# BigFrontplane.net
KiCad netlist of a schematic drawn in EAGLE
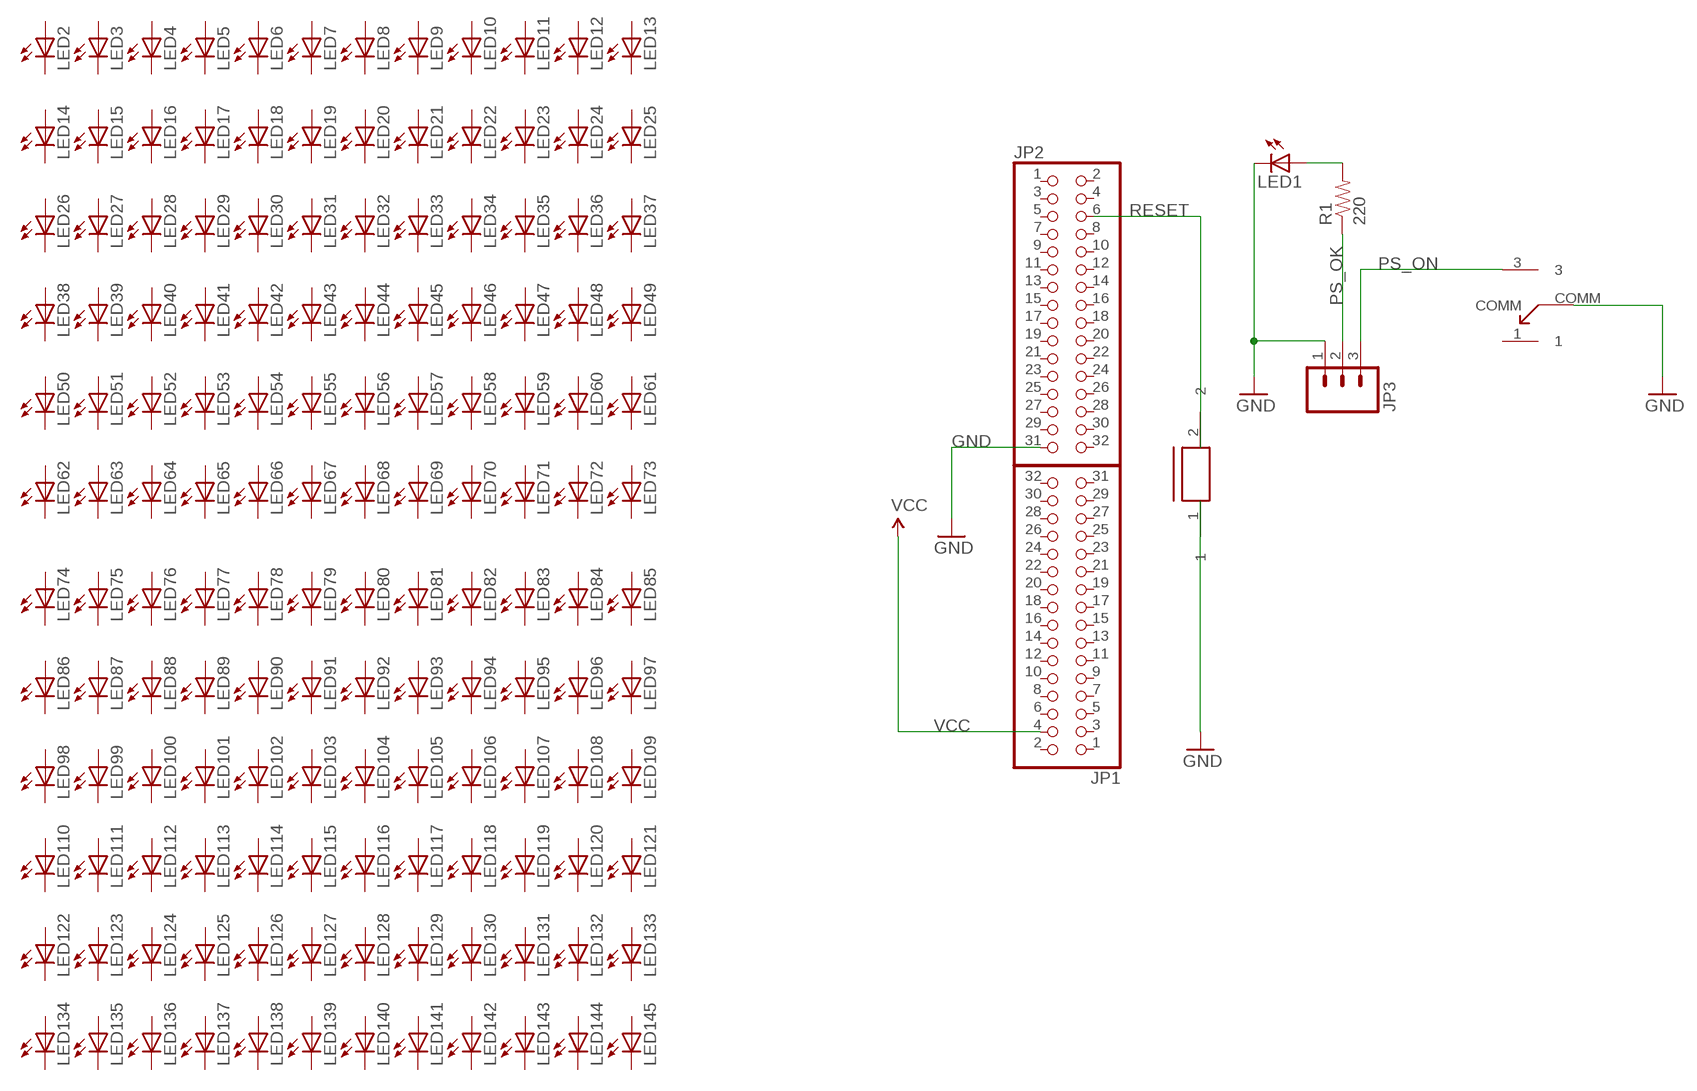
[diagram p0: schematic, sheet 1]

(export (version "E")
  (design (tool "Eeschema 10.0.6"))
  (components
    (comp (ref "JP1")
      (value "PINHD-2X16")
      (footprint "eagle-import:2X16")
      (libsource (lib "eagle-import") (part "PINHD-2X16"))
    )
    (comp (ref "JP2")
      (value "PINHD-2X16")
      (footprint "eagle-import:2X16")
      (libsource (lib "eagle-import") (part "PINHD-2X16"))
    )
    (comp (ref "JP3")
      (value "M03LONGPADS")
      (footprint "eagle-import:1X03_LONGPADS")
      (libsource (lib "eagle-import") (part "M03LONGPADS"))
    )
    (comp (ref "LED1")
      (value "LED5MM")
      (footprint "eagle-import:LED5MM")
      (libsource (lib "eagle-import") (part "led_LED5MM"))
    )
    (comp (ref "LED2")
      (value "LED3MM")
      (footprint "eagle-import:LED3MM")
      (libsource (lib "eagle-import") (part "LED3MM"))
    )
    (comp (ref "LED3")
      (value "LED3MM")
      (footprint "eagle-import:LED3MM")
      (libsource (lib "eagle-import") (part "LED3MM"))
    )
    (comp (ref "LED4")
      (value "LED3MM")
      (footprint "eagle-import:LED3MM")
      (libsource (lib "eagle-import") (part "LED3MM"))
    )
    (comp (ref "LED5")
      (value "LED3MM")
      (footprint "eagle-import:LED3MM")
      (libsource (lib "eagle-import") (part "LED3MM"))
    )
    (comp (ref "LED6")
      (value "LED3MM")
      (footprint "eagle-import:LED3MM")
      (libsource (lib "eagle-import") (part "LED3MM"))
    )
    (comp (ref "LED7")
      (value "LED3MM")
      (footprint "eagle-import:LED3MM")
      (libsource (lib "eagle-import") (part "LED3MM"))
    )
    (comp (ref "LED8")
      (value "LED3MM")
      (footprint "eagle-import:LED3MM")
      (libsource (lib "eagle-import") (part "LED3MM"))
    )
    (comp (ref "LED9")
      (value "LED3MM")
      (footprint "eagle-import:LED3MM")
      (libsource (lib "eagle-import") (part "LED3MM"))
    )
    (comp (ref "LED10")
      (value "LED3MM")
      (footprint "eagle-import:LED3MM")
      (libsource (lib "eagle-import") (part "LED3MM"))
    )
    (comp (ref "LED11")
      (value "LED3MM")
      (footprint "eagle-import:LED3MM")
      (libsource (lib "eagle-import") (part "LED3MM"))
    )
    (comp (ref "LED12")
      (value "LED3MM")
      (footprint "eagle-import:LED3MM")
      (libsource (lib "eagle-import") (part "LED3MM"))
    )
    (comp (ref "LED13")
      (value "LED3MM")
      (footprint "eagle-import:LED3MM")
      (libsource (lib "eagle-import") (part "LED3MM"))
    )
    (comp (ref "LED14")
      (value "LED3MM")
      (footprint "eagle-import:LED3MM")
      (libsource (lib "eagle-import") (part "LED3MM"))
    )
    (comp (ref "LED15")
      (value "LED3MM")
      (footprint "eagle-import:LED3MM")
      (libsource (lib "eagle-import") (part "LED3MM"))
    )
    (comp (ref "LED16")
      (value "LED3MM")
      (footprint "eagle-import:LED3MM")
      (libsource (lib "eagle-import") (part "LED3MM"))
    )
    (comp (ref "LED17")
      (value "LED3MM")
      (footprint "eagle-import:LED3MM")
      (libsource (lib "eagle-import") (part "LED3MM"))
    )
    (comp (ref "LED18")
      (value "LED3MM")
      (footprint "eagle-import:LED3MM")
      (libsource (lib "eagle-import") (part "LED3MM"))
    )
    (comp (ref "LED19")
      (value "LED3MM")
      (footprint "eagle-import:LED3MM")
      (libsource (lib "eagle-import") (part "LED3MM"))
    )
    (comp (ref "LED20")
      (value "LED3MM")
      (footprint "eagle-import:LED3MM")
      (libsource (lib "eagle-import") (part "LED3MM"))
    )
    (comp (ref "LED21")
      (value "LED3MM")
      (footprint "eagle-import:LED3MM")
      (libsource (lib "eagle-import") (part "LED3MM"))
    )
    (comp (ref "LED22")
      (value "LED3MM")
      (footprint "eagle-import:LED3MM")
      (libsource (lib "eagle-import") (part "LED3MM"))
    )
    (comp (ref "LED23")
      (value "LED3MM")
      (footprint "eagle-import:LED3MM")
      (libsource (lib "eagle-import") (part "LED3MM"))
    )
    (comp (ref "LED24")
      (value "LED3MM")
      (footprint "eagle-import:LED3MM")
      (libsource (lib "eagle-import") (part "LED3MM"))
    )
    (comp (ref "LED25")
      (value "LED3MM")
      (footprint "eagle-import:LED3MM")
      (libsource (lib "eagle-import") (part "LED3MM"))
    )
    (comp (ref "LED26")
      (value "LED3MM")
      (footprint "eagle-import:LED3MM")
      (libsource (lib "eagle-import") (part "LED3MM"))
    )
    (comp (ref "LED27")
      (value "LED3MM")
      (footprint "eagle-import:LED3MM")
      (libsource (lib "eagle-import") (part "LED3MM"))
    )
    (comp (ref "LED28")
      (value "LED3MM")
      (footprint "eagle-import:LED3MM")
      (libsource (lib "eagle-import") (part "LED3MM"))
    )
    (comp (ref "LED29")
      (value "LED3MM")
      (footprint "eagle-import:LED3MM")
      (libsource (lib "eagle-import") (part "LED3MM"))
    )
    (comp (ref "LED30")
      (value "LED3MM")
      (footprint "eagle-import:LED3MM")
      (libsource (lib "eagle-import") (part "LED3MM"))
    )
    (comp (ref "LED31")
      (value "LED3MM")
      (footprint "eagle-import:LED3MM")
      (libsource (lib "eagle-import") (part "LED3MM"))
    )
    (comp (ref "LED32")
      (value "LED3MM")
      (footprint "eagle-import:LED3MM")
      (libsource (lib "eagle-import") (part "LED3MM"))
    )
    (comp (ref "LED33")
      (value "LED3MM")
      (footprint "eagle-import:LED3MM")
      (libsource (lib "eagle-import") (part "LED3MM"))
    )
    (comp (ref "LED34")
      (value "LED3MM")
      (footprint "eagle-import:LED3MM")
      (libsource (lib "eagle-import") (part "LED3MM"))
    )
    (comp (ref "LED35")
      (value "LED3MM")
      (footprint "eagle-import:LED3MM")
      (libsource (lib "eagle-import") (part "LED3MM"))
    )
    (comp (ref "LED36")
      (value "LED3MM")
      (footprint "eagle-import:LED3MM")
      (libsource (lib "eagle-import") (part "LED3MM"))
    )
    (comp (ref "LED37")
      (value "LED3MM")
      (footprint "eagle-import:LED3MM")
      (libsource (lib "eagle-import") (part "LED3MM"))
    )
    (comp (ref "LED38")
      (value "LED3MM")
      (footprint "eagle-import:LED3MM")
      (libsource (lib "eagle-import") (part "LED3MM"))
    )
    (comp (ref "LED39")
      (value "LED3MM")
      (footprint "eagle-import:LED3MM")
      (libsource (lib "eagle-import") (part "LED3MM"))
    )
    (comp (ref "LED40")
      (value "LED3MM")
      (footprint "eagle-import:LED3MM")
      (libsource (lib "eagle-import") (part "LED3MM"))
    )
    (comp (ref "LED41")
      (value "LED3MM")
      (footprint "eagle-import:LED3MM")
      (libsource (lib "eagle-import") (part "LED3MM"))
    )
    (comp (ref "LED42")
      (value "LED3MM")
      (footprint "eagle-import:LED3MM")
      (libsource (lib "eagle-import") (part "LED3MM"))
    )
    (comp (ref "LED43")
      (value "LED3MM")
      (footprint "eagle-import:LED3MM")
      (libsource (lib "eagle-import") (part "LED3MM"))
    )
    (comp (ref "LED44")
      (value "LED3MM")
      (footprint "eagle-import:LED3MM")
      (libsource (lib "eagle-import") (part "LED3MM"))
    )
    (comp (ref "LED45")
      (value "LED3MM")
      (footprint "eagle-import:LED3MM")
      (libsource (lib "eagle-import") (part "LED3MM"))
    )
    (comp (ref "LED46")
      (value "LED3MM")
      (footprint "eagle-import:LED3MM")
      (libsource (lib "eagle-import") (part "LED3MM"))
    )
    (comp (ref "LED47")
      (value "LED3MM")
      (footprint "eagle-import:LED3MM")
      (libsource (lib "eagle-import") (part "LED3MM"))
    )
    (comp (ref "LED48")
      (value "LED3MM")
      (footprint "eagle-import:LED3MM")
      (libsource (lib "eagle-import") (part "LED3MM"))
    )
    (comp (ref "LED49")
      (value "LED3MM")
      (footprint "eagle-import:LED3MM")
      (libsource (lib "eagle-import") (part "LED3MM"))
    )
    (comp (ref "LED50")
      (value "LED3MM")
      (footprint "eagle-import:LED3MM")
      (libsource (lib "eagle-import") (part "LED3MM"))
    )
    (comp (ref "LED51")
      (value "LED3MM")
      (footprint "eagle-import:LED3MM")
      (libsource (lib "eagle-import") (part "LED3MM"))
    )
    (comp (ref "LED52")
      (value "LED3MM")
      (footprint "eagle-import:LED3MM")
      (libsource (lib "eagle-import") (part "LED3MM"))
    )
    (comp (ref "LED53")
      (value "LED3MM")
      (footprint "eagle-import:LED3MM")
      (libsource (lib "eagle-import") (part "LED3MM"))
    )
    (comp (ref "LED54")
      (value "LED3MM")
      (footprint "eagle-import:LED3MM")
      (libsource (lib "eagle-import") (part "LED3MM"))
    )
    (comp (ref "LED55")
      (value "LED3MM")
      (footprint "eagle-import:LED3MM")
      (libsource (lib "eagle-import") (part "LED3MM"))
    )
    (comp (ref "LED56")
      (value "LED3MM")
      (footprint "eagle-import:LED3MM")
      (libsource (lib "eagle-import") (part "LED3MM"))
    )
    (comp (ref "LED57")
      (value "LED3MM")
      (footprint "eagle-import:LED3MM")
      (libsource (lib "eagle-import") (part "LED3MM"))
    )
    (comp (ref "LED58")
      (value "LED3MM")
      (footprint "eagle-import:LED3MM")
      (libsource (lib "eagle-import") (part "LED3MM"))
    )
    (comp (ref "LED59")
      (value "LED3MM")
      (footprint "eagle-import:LED3MM")
      (libsource (lib "eagle-import") (part "LED3MM"))
    )
    (comp (ref "LED60")
      (value "LED3MM")
      (footprint "eagle-import:LED3MM")
      (libsource (lib "eagle-import") (part "LED3MM"))
    )
    (comp (ref "LED61")
      (value "LED3MM")
      (footprint "eagle-import:LED3MM")
      (libsource (lib "eagle-import") (part "LED3MM"))
    )
    (comp (ref "LED62")
      (value "LED3MM")
      (footprint "eagle-import:LED3MM")
      (libsource (lib "eagle-import") (part "LED3MM"))
    )
    (comp (ref "LED63")
      (value "LED3MM")
      (footprint "eagle-import:LED3MM")
      (libsource (lib "eagle-import") (part "LED3MM"))
    )
    (comp (ref "LED64")
      (value "LED3MM")
      (footprint "eagle-import:LED3MM")
      (libsource (lib "eagle-import") (part "LED3MM"))
    )
    (comp (ref "LED65")
      (value "LED3MM")
      (footprint "eagle-import:LED3MM")
      (libsource (lib "eagle-import") (part "LED3MM"))
    )
    (comp (ref "LED66")
      (value "LED3MM")
      (footprint "eagle-import:LED3MM")
      (libsource (lib "eagle-import") (part "LED3MM"))
    )
    (comp (ref "LED67")
      (value "LED3MM")
      (footprint "eagle-import:LED3MM")
      (libsource (lib "eagle-import") (part "LED3MM"))
    )
    (comp (ref "LED68")
      (value "LED3MM")
      (footprint "eagle-import:LED3MM")
      (libsource (lib "eagle-import") (part "LED3MM"))
    )
    (comp (ref "LED69")
      (value "LED3MM")
      (footprint "eagle-import:LED3MM")
      (libsource (lib "eagle-import") (part "LED3MM"))
    )
    (comp (ref "LED70")
      (value "LED3MM")
      (footprint "eagle-import:LED3MM")
      (libsource (lib "eagle-import") (part "LED3MM"))
    )
    (comp (ref "LED71")
      (value "LED3MM")
      (footprint "eagle-import:LED3MM")
      (libsource (lib "eagle-import") (part "LED3MM"))
    )
    (comp (ref "LED72")
      (value "LED3MM")
      (footprint "eagle-import:LED3MM")
      (libsource (lib "eagle-import") (part "LED3MM"))
    )
    (comp (ref "LED73")
      (value "LED3MM")
      (footprint "eagle-import:LED3MM")
      (libsource (lib "eagle-import") (part "LED3MM"))
    )
    (comp (ref "LED74")
      (value "LED3MM")
      (footprint "eagle-import:LED3MM")
      (libsource (lib "eagle-import") (part "LED3MM"))
    )
    (comp (ref "LED75")
      (value "LED3MM")
      (footprint "eagle-import:LED3MM")
      (libsource (lib "eagle-import") (part "LED3MM"))
    )
    (comp (ref "LED76")
      (value "LED3MM")
      (footprint "eagle-import:LED3MM")
      (libsource (lib "eagle-import") (part "LED3MM"))
    )
    (comp (ref "LED77")
      (value "LED3MM")
      (footprint "eagle-import:LED3MM")
      (libsource (lib "eagle-import") (part "LED3MM"))
    )
    (comp (ref "LED78")
      (value "LED3MM")
      (footprint "eagle-import:LED3MM")
      (libsource (lib "eagle-import") (part "LED3MM"))
    )
    (comp (ref "LED79")
      (value "LED3MM")
      (footprint "eagle-import:LED3MM")
      (libsource (lib "eagle-import") (part "LED3MM"))
    )
    (comp (ref "LED80")
      (value "LED3MM")
      (footprint "eagle-import:LED3MM")
      (libsource (lib "eagle-import") (part "LED3MM"))
    )
    (comp (ref "LED81")
      (value "LED3MM")
      (footprint "eagle-import:LED3MM")
      (libsource (lib "eagle-import") (part "LED3MM"))
    )
    (comp (ref "LED82")
      (value "LED3MM")
      (footprint "eagle-import:LED3MM")
      (libsource (lib "eagle-import") (part "LED3MM"))
    )
    (comp (ref "LED83")
      (value "LED3MM")
      (footprint "eagle-import:LED3MM")
      (libsource (lib "eagle-import") (part "LED3MM"))
    )
    (comp (ref "LED84")
      (value "LED3MM")
      (footprint "eagle-import:LED3MM")
      (libsource (lib "eagle-import") (part "LED3MM"))
    )
    (comp (ref "LED85")
      (value "LED3MM")
      (footprint "eagle-import:LED3MM")
      (libsource (lib "eagle-import") (part "LED3MM"))
    )
    (comp (ref "LED86")
      (value "LED3MM")
      (footprint "eagle-import:LED3MM")
      (libsource (lib "eagle-import") (part "LED3MM"))
    )
    (comp (ref "LED87")
      (value "LED3MM")
      (footprint "eagle-import:LED3MM")
      (libsource (lib "eagle-import") (part "LED3MM"))
    )
    (comp (ref "LED88")
      (value "LED3MM")
      (footprint "eagle-import:LED3MM")
      (libsource (lib "eagle-import") (part "LED3MM"))
    )
    (comp (ref "LED89")
      (value "LED3MM")
      (footprint "eagle-import:LED3MM")
      (libsource (lib "eagle-import") (part "LED3MM"))
    )
    (comp (ref "LED90")
      (value "LED3MM")
      (footprint "eagle-import:LED3MM")
      (libsource (lib "eagle-import") (part "LED3MM"))
    )
    (comp (ref "LED91")
      (value "LED3MM")
      (footprint "eagle-import:LED3MM")
      (libsource (lib "eagle-import") (part "LED3MM"))
    )
    (comp (ref "LED92")
      (value "LED3MM")
      (footprint "eagle-import:LED3MM")
      (libsource (lib "eagle-import") (part "LED3MM"))
    )
    (comp (ref "LED93")
      (value "LED3MM")
      (footprint "eagle-import:LED3MM")
      (libsource (lib "eagle-import") (part "LED3MM"))
    )
    (comp (ref "LED94")
      (value "LED3MM")
      (footprint "eagle-import:LED3MM")
      (libsource (lib "eagle-import") (part "LED3MM"))
    )
    (comp (ref "LED95")
      (value "LED3MM")
      (footprint "eagle-import:LED3MM")
      (libsource (lib "eagle-import") (part "LED3MM"))
    )
    (comp (ref "LED96")
      (value "LED3MM")
      (footprint "eagle-import:LED3MM")
      (libsource (lib "eagle-import") (part "LED3MM"))
    )
    (comp (ref "LED97")
      (value "LED3MM")
      (footprint "eagle-import:LED3MM")
      (libsource (lib "eagle-import") (part "LED3MM"))
    )
    (comp (ref "LED98")
      (value "LED3MM")
      (footprint "eagle-import:LED3MM")
      (libsource (lib "eagle-import") (part "LED3MM"))
    )
    (comp (ref "LED99")
      (value "LED3MM")
      (footprint "eagle-import:LED3MM")
      (libsource (lib "eagle-import") (part "LED3MM"))
    )
    (comp (ref "LED100")
      (value "LED3MM")
      (footprint "eagle-import:LED3MM")
      (libsource (lib "eagle-import") (part "LED3MM"))
    )
    (comp (ref "LED101")
      (value "LED3MM")
      (footprint "eagle-import:LED3MM")
      (libsource (lib "eagle-import") (part "LED3MM"))
    )
    (comp (ref "LED102")
      (value "LED3MM")
      (footprint "eagle-import:LED3MM")
      (libsource (lib "eagle-import") (part "LED3MM"))
    )
    (comp (ref "LED103")
      (value "LED3MM")
      (footprint "eagle-import:LED3MM")
      (libsource (lib "eagle-import") (part "LED3MM"))
    )
    (comp (ref "LED104")
      (value "LED3MM")
      (footprint "eagle-import:LED3MM")
      (libsource (lib "eagle-import") (part "LED3MM"))
    )
    (comp (ref "LED105")
      (value "LED3MM")
      (footprint "eagle-import:LED3MM")
      (libsource (lib "eagle-import") (part "LED3MM"))
    )
    (comp (ref "LED106")
      (value "LED3MM")
      (footprint "eagle-import:LED3MM")
      (libsource (lib "eagle-import") (part "LED3MM"))
    )
    (comp (ref "LED107")
      (value "LED3MM")
      (footprint "eagle-import:LED3MM")
      (libsource (lib "eagle-import") (part "LED3MM"))
    )
    (comp (ref "LED108")
      (value "LED3MM")
      (footprint "eagle-import:LED3MM")
      (libsource (lib "eagle-import") (part "LED3MM"))
    )
    (comp (ref "LED109")
      (value "LED3MM")
      (footprint "eagle-import:LED3MM")
      (libsource (lib "eagle-import") (part "LED3MM"))
    )
    (comp (ref "LED110")
      (value "LED3MM")
      (footprint "eagle-import:LED3MM")
      (libsource (lib "eagle-import") (part "LED3MM"))
    )
    (comp (ref "LED111")
      (value "LED3MM")
      (footprint "eagle-import:LED3MM")
      (libsource (lib "eagle-import") (part "LED3MM"))
    )
    (comp (ref "LED112")
      (value "LED3MM")
      (footprint "eagle-import:LED3MM")
      (libsource (lib "eagle-import") (part "LED3MM"))
    )
    (comp (ref "LED113")
      (value "LED3MM")
      (footprint "eagle-import:LED3MM")
      (libsource (lib "eagle-import") (part "LED3MM"))
    )
    (comp (ref "LED114")
      (value "LED3MM")
      (footprint "eagle-import:LED3MM")
      (libsource (lib "eagle-import") (part "LED3MM"))
    )
    (comp (ref "LED115")
      (value "LED3MM")
      (footprint "eagle-import:LED3MM")
      (libsource (lib "eagle-import") (part "LED3MM"))
    )
    (comp (ref "LED116")
      (value "LED3MM")
      (footprint "eagle-import:LED3MM")
      (libsource (lib "eagle-import") (part "LED3MM"))
    )
    (comp (ref "LED117")
      (value "LED3MM")
      (footprint "eagle-import:LED3MM")
      (libsource (lib "eagle-import") (part "LED3MM"))
    )
    (comp (ref "LED118")
      (value "LED3MM")
      (footprint "eagle-import:LED3MM")
      (libsource (lib "eagle-import") (part "LED3MM"))
    )
    (comp (ref "LED119")
      (value "LED3MM")
      (footprint "eagle-import:LED3MM")
      (libsource (lib "eagle-import") (part "LED3MM"))
    )
    (comp (ref "LED120")
      (value "LED3MM")
      (footprint "eagle-import:LED3MM")
      (libsource (lib "eagle-import") (part "LED3MM"))
    )
    (comp (ref "LED121")
      (value "LED3MM")
      (footprint "eagle-import:LED3MM")
      (libsource (lib "eagle-import") (part "LED3MM"))
    )
    (comp (ref "LED122")
      (value "LED3MM")
      (footprint "eagle-import:LED3MM")
      (libsource (lib "eagle-import") (part "LED3MM"))
    )
    (comp (ref "LED123")
      (value "LED3MM")
      (footprint "eagle-import:LED3MM")
      (libsource (lib "eagle-import") (part "LED3MM"))
    )
    (comp (ref "LED124")
      (value "LED3MM")
      (footprint "eagle-import:LED3MM")
      (libsource (lib "eagle-import") (part "LED3MM"))
    )
    (comp (ref "LED125")
      (value "LED3MM")
      (footprint "eagle-import:LED3MM")
      (libsource (lib "eagle-import") (part "LED3MM"))
    )
    (comp (ref "LED126")
      (value "LED3MM")
      (footprint "eagle-import:LED3MM")
      (libsource (lib "eagle-import") (part "LED3MM"))
    )
    (comp (ref "LED127")
      (value "LED3MM")
      (footprint "eagle-import:LED3MM")
      (libsource (lib "eagle-import") (part "LED3MM"))
    )
    (comp (ref "LED128")
      (value "LED3MM")
      (footprint "eagle-import:LED3MM")
      (libsource (lib "eagle-import") (part "LED3MM"))
    )
    (comp (ref "LED129")
      (value "LED3MM")
      (footprint "eagle-import:LED3MM")
      (libsource (lib "eagle-import") (part "LED3MM"))
    )
    (comp (ref "LED130")
      (value "LED3MM")
      (footprint "eagle-import:LED3MM")
      (libsource (lib "eagle-import") (part "LED3MM"))
    )
    (comp (ref "LED131")
      (value "LED3MM")
      (footprint "eagle-import:LED3MM")
      (libsource (lib "eagle-import") (part "LED3MM"))
    )
    (comp (ref "LED132")
      (value "LED3MM")
      (footprint "eagle-import:LED3MM")
      (libsource (lib "eagle-import") (part "LED3MM"))
    )
    (comp (ref "LED133")
      (value "LED3MM")
      (footprint "eagle-import:LED3MM")
      (libsource (lib "eagle-import") (part "LED3MM"))
    )
    (comp (ref "LED134")
      (value "LED3MM")
      (footprint "eagle-import:LED3MM")
      (libsource (lib "eagle-import") (part "LED3MM"))
    )
    (comp (ref "LED135")
      (value "LED3MM")
      (footprint "eagle-import:LED3MM")
      (libsource (lib "eagle-import") (part "LED3MM"))
    )
    (comp (ref "LED136")
      (value "LED3MM")
      (footprint "eagle-import:LED3MM")
      (libsource (lib "eagle-import") (part "LED3MM"))
    )
    (comp (ref "LED137")
      (value "LED3MM")
      (footprint "eagle-import:LED3MM")
      (libsource (lib "eagle-import") (part "LED3MM"))
    )
    (comp (ref "LED138")
      (value "LED3MM")
      (footprint "eagle-import:LED3MM")
      (libsource (lib "eagle-import") (part "LED3MM"))
    )
    (comp (ref "LED139")
      (value "LED3MM")
      (footprint "eagle-import:LED3MM")
      (libsource (lib "eagle-import") (part "LED3MM"))
    )
    (comp (ref "LED140")
      (value "LED3MM")
      (footprint "eagle-import:LED3MM")
      (libsource (lib "eagle-import") (part "LED3MM"))
    )
    (comp (ref "LED141")
      (value "LED3MM")
      (footprint "eagle-import:LED3MM")
      (libsource (lib "eagle-import") (part "LED3MM"))
    )
    (comp (ref "LED142")
      (value "LED3MM")
      (footprint "eagle-import:LED3MM")
      (libsource (lib "eagle-import") (part "LED3MM"))
    )
    (comp (ref "LED143")
      (value "LED3MM")
      (footprint "eagle-import:LED3MM")
      (libsource (lib "eagle-import") (part "LED3MM"))
    )
    (comp (ref "LED144")
      (value "LED3MM")
      (footprint "eagle-import:LED3MM")
      (libsource (lib "eagle-import") (part "LED3MM"))
    )
    (comp (ref "LED145")
      (value "LED3MM")
      (footprint "eagle-import:LED3MM")
      (libsource (lib "eagle-import") (part "LED3MM"))
    )
    (comp (ref "R1")
      (value "220")
      (footprint "eagle-import:AXIAL-0.3-KIT")
      (libsource (lib "eagle-import") (part "RESISTORKIT"))
    )
    (comp (ref "U$1")
      (value "7101")
      (footprint "eagle-import:7101SYCQE")
      (libsource (lib "eagle-import") (part "7101"))
    )
    (comp (ref "U$2")
      (value "TP11")
      (footprint "eagle-import:TP11")
      (libsource (lib "eagle-import") (part "TP11"))
    )
  )
  (nets
    (net (code "1") (name "/PS_OK") (class "Default")
      (node (ref "JP3") (pin "2") (pinfunction "2_2") (pintype "passive"))
      (node (ref "R1") (pin "P$1") (pinfunction "1_P$1") (pintype "passive"))
    )
    (net (code "2") (name "/PS_ON") (class "Default")
      (node (ref "JP3") (pin "3") (pinfunction "3_3") (pintype "passive"))
      (node (ref "U$1") (pin "3") (pinfunction "3_3") (pintype "bidirectional"))
    )
    (net (code "3") (name "/RESET") (class "Default")
      (node (ref "JP2") (pin "6") (pinfunction "6_6") (pintype "passive"))
      (node (ref "U$2") (pin "2") (pinfunction "2_2") (pintype "bidirectional"))
    )
    (net (code "4") (name "GND") (class "Default")
      (node (ref "JP2") (pin "31") (pinfunction "31_31") (pintype "passive"))
      (node (ref "JP3") (pin "1") (pinfunction "1_1") (pintype "passive"))
      (node (ref "LED1") (pin "K") (pinfunction "C_K") (pintype "passive"))
      (node (ref "U$1") (pin "COMM") (pinfunction "COMM_COMM") (pintype "bidirectional"))
      (node (ref "U$2") (pin "1") (pinfunction "1_1") (pintype "bidirectional"))
    )
    (net (code "5") (name "Net-(R1-2)") (class "Default")
      (node (ref "LED1") (pin "A") (pinfunction "A_A") (pintype "passive"))
      (node (ref "R1") (pin "P$2") (pinfunction "2_P$2") (pintype "passive"))
    )
    (net (code "6") (name "VCC") (class "Default")
      (node (ref "JP1") (pin "4") (pinfunction "4_4") (pintype "passive"))
    )
    (net (code "7") (name "unconnected-(JP1-Pad1)") (class "Default")
      (node (ref "JP1") (pin "1") (pinfunction "1_1") (pintype "passive"))
    )
    (net (code "8") (name "unconnected-(JP1-Pad2)") (class "Default")
      (node (ref "JP1") (pin "2") (pinfunction "2_2") (pintype "passive"))
    )
    (net (code "9") (name "unconnected-(JP1-Pad3)") (class "Default")
      (node (ref "JP1") (pin "3") (pinfunction "3_3") (pintype "passive"))
    )
    (net (code "10") (name "unconnected-(JP1-Pad5)") (class "Default")
      (node (ref "JP1") (pin "5") (pinfunction "5_5") (pintype "passive"))
    )
    (net (code "11") (name "unconnected-(JP1-Pad6)") (class "Default")
      (node (ref "JP1") (pin "6") (pinfunction "6_6") (pintype "passive"))
    )
    (net (code "12") (name "unconnected-(JP1-Pad7)") (class "Default")
      (node (ref "JP1") (pin "7") (pinfunction "7_7") (pintype "passive"))
    )
    (net (code "13") (name "unconnected-(JP1-Pad8)") (class "Default")
      (node (ref "JP1") (pin "8") (pinfunction "8_8") (pintype "passive"))
    )
    (net (code "14") (name "unconnected-(JP1-Pad9)") (class "Default")
      (node (ref "JP1") (pin "9") (pinfunction "9_9") (pintype "passive"))
    )
    (net (code "15") (name "unconnected-(JP1-Pad10)") (class "Default")
      (node (ref "JP1") (pin "10") (pinfunction "10_10") (pintype "passive"))
    )
    (net (code "16") (name "unconnected-(JP1-Pad11)") (class "Default")
      (node (ref "JP1") (pin "11") (pinfunction "11_11") (pintype "passive"))
    )
    (net (code "17") (name "unconnected-(JP1-Pad12)") (class "Default")
      (node (ref "JP1") (pin "12") (pinfunction "12_12") (pintype "passive"))
    )
    (net (code "18") (name "unconnected-(JP1-Pad13)") (class "Default")
      (node (ref "JP1") (pin "13") (pinfunction "13_13") (pintype "passive"))
    )
    (net (code "19") (name "unconnected-(JP1-Pad14)") (class "Default")
      (node (ref "JP1") (pin "14") (pinfunction "14_14") (pintype "passive"))
    )
    (net (code "20") (name "unconnected-(JP1-Pad15)") (class "Default")
      (node (ref "JP1") (pin "15") (pinfunction "15_15") (pintype "passive"))
    )
    (net (code "21") (name "unconnected-(JP1-Pad16)") (class "Default")
      (node (ref "JP1") (pin "16") (pinfunction "16_16") (pintype "passive"))
    )
    (net (code "22") (name "unconnected-(JP1-Pad17)") (class "Default")
      (node (ref "JP1") (pin "17") (pinfunction "17_17") (pintype "passive"))
    )
    (net (code "23") (name "unconnected-(JP1-Pad18)") (class "Default")
      (node (ref "JP1") (pin "18") (pinfunction "18_18") (pintype "passive"))
    )
    (net (code "24") (name "unconnected-(JP1-Pad19)") (class "Default")
      (node (ref "JP1") (pin "19") (pinfunction "19_19") (pintype "passive"))
    )
    (net (code "25") (name "unconnected-(JP1-Pad20)") (class "Default")
      (node (ref "JP1") (pin "20") (pinfunction "20_20") (pintype "passive"))
    )
    (net (code "26") (name "unconnected-(JP1-Pad21)") (class "Default")
      (node (ref "JP1") (pin "21") (pinfunction "21_21") (pintype "passive"))
    )
    (net (code "27") (name "unconnected-(JP1-Pad22)") (class "Default")
      (node (ref "JP1") (pin "22") (pinfunction "22_22") (pintype "passive"))
    )
    (net (code "28") (name "unconnected-(JP1-Pad23)") (class "Default")
      (node (ref "JP1") (pin "23") (pinfunction "23_23") (pintype "passive"))
    )
    (net (code "29") (name "unconnected-(JP1-Pad24)") (class "Default")
      (node (ref "JP1") (pin "24") (pinfunction "24_24") (pintype "passive"))
    )
    (net (code "30") (name "unconnected-(JP1-Pad25)") (class "Default")
      (node (ref "JP1") (pin "25") (pinfunction "25_25") (pintype "passive"))
    )
    (net (code "31") (name "unconnected-(JP1-Pad26)") (class "Default")
      (node (ref "JP1") (pin "26") (pinfunction "26_26") (pintype "passive"))
    )
    (net (code "32") (name "unconnected-(JP1-Pad27)") (class "Default")
      (node (ref "JP1") (pin "27") (pinfunction "27_27") (pintype "passive"))
    )
    (net (code "33") (name "unconnected-(JP1-Pad28)") (class "Default")
      (node (ref "JP1") (pin "28") (pinfunction "28_28") (pintype "passive"))
    )
    (net (code "34") (name "unconnected-(JP1-Pad29)") (class "Default")
      (node (ref "JP1") (pin "29") (pinfunction "29_29") (pintype "passive"))
    )
    (net (code "35") (name "unconnected-(JP1-Pad30)") (class "Default")
      (node (ref "JP1") (pin "30") (pinfunction "30_30") (pintype "passive"))
    )
    (net (code "36") (name "unconnected-(JP1-Pad31)") (class "Default")
      (node (ref "JP1") (pin "31") (pinfunction "31_31") (pintype "passive"))
    )
    (net (code "37") (name "unconnected-(JP1-Pad32)") (class "Default")
      (node (ref "JP1") (pin "32") (pinfunction "32_32") (pintype "passive"))
    )
    (net (code "38") (name "unconnected-(JP2-Pad1)") (class "Default")
      (node (ref "JP2") (pin "1") (pinfunction "1_1") (pintype "passive"))
    )
    (net (code "39") (name "unconnected-(JP2-Pad2)") (class "Default")
      (node (ref "JP2") (pin "2") (pinfunction "2_2") (pintype "passive"))
    )
    (net (code "40") (name "unconnected-(JP2-Pad3)") (class "Default")
      (node (ref "JP2") (pin "3") (pinfunction "3_3") (pintype "passive"))
    )
    (net (code "41") (name "unconnected-(JP2-Pad4)") (class "Default")
      (node (ref "JP2") (pin "4") (pinfunction "4_4") (pintype "passive"))
    )
    (net (code "42") (name "unconnected-(JP2-Pad5)") (class "Default")
      (node (ref "JP2") (pin "5") (pinfunction "5_5") (pintype "passive"))
    )
    (net (code "43") (name "unconnected-(JP2-Pad7)") (class "Default")
      (node (ref "JP2") (pin "7") (pinfunction "7_7") (pintype "passive"))
    )
    (net (code "44") (name "unconnected-(JP2-Pad8)") (class "Default")
      (node (ref "JP2") (pin "8") (pinfunction "8_8") (pintype "passive"))
    )
    (net (code "45") (name "unconnected-(JP2-Pad9)") (class "Default")
      (node (ref "JP2") (pin "9") (pinfunction "9_9") (pintype "passive"))
    )
    (net (code "46") (name "unconnected-(JP2-Pad10)") (class "Default")
      (node (ref "JP2") (pin "10") (pinfunction "10_10") (pintype "passive"))
    )
    (net (code "47") (name "unconnected-(JP2-Pad11)") (class "Default")
      (node (ref "JP2") (pin "11") (pinfunction "11_11") (pintype "passive"))
    )
    (net (code "48") (name "unconnected-(JP2-Pad12)") (class "Default")
      (node (ref "JP2") (pin "12") (pinfunction "12_12") (pintype "passive"))
    )
    (net (code "49") (name "unconnected-(JP2-Pad13)") (class "Default")
      (node (ref "JP2") (pin "13") (pinfunction "13_13") (pintype "passive"))
    )
    (net (code "50") (name "unconnected-(JP2-Pad14)") (class "Default")
      (node (ref "JP2") (pin "14") (pinfunction "14_14") (pintype "passive"))
    )
    (net (code "51") (name "unconnected-(JP2-Pad15)") (class "Default")
      (node (ref "JP2") (pin "15") (pinfunction "15_15") (pintype "passive"))
    )
    (net (code "52") (name "unconnected-(JP2-Pad16)") (class "Default")
      (node (ref "JP2") (pin "16") (pinfunction "16_16") (pintype "passive"))
    )
    (net (code "53") (name "unconnected-(JP2-Pad17)") (class "Default")
      (node (ref "JP2") (pin "17") (pinfunction "17_17") (pintype "passive"))
    )
    (net (code "54") (name "unconnected-(JP2-Pad18)") (class "Default")
      (node (ref "JP2") (pin "18") (pinfunction "18_18") (pintype "passive"))
    )
    (net (code "55") (name "unconnected-(JP2-Pad19)") (class "Default")
      (node (ref "JP2") (pin "19") (pinfunction "19_19") (pintype "passive"))
    )
    (net (code "56") (name "unconnected-(JP2-Pad20)") (class "Default")
      (node (ref "JP2") (pin "20") (pinfunction "20_20") (pintype "passive"))
    )
    (net (code "57") (name "unconnected-(JP2-Pad21)") (class "Default")
      (node (ref "JP2") (pin "21") (pinfunction "21_21") (pintype "passive"))
    )
    (net (code "58") (name "unconnected-(JP2-Pad22)") (class "Default")
      (node (ref "JP2") (pin "22") (pinfunction "22_22") (pintype "passive"))
    )
    (net (code "59") (name "unconnected-(JP2-Pad23)") (class "Default")
      (node (ref "JP2") (pin "23") (pinfunction "23_23") (pintype "passive"))
    )
    (net (code "60") (name "unconnected-(JP2-Pad24)") (class "Default")
      (node (ref "JP2") (pin "24") (pinfunction "24_24") (pintype "passive"))
    )
    (net (code "61") (name "unconnected-(JP2-Pad25)") (class "Default")
      (node (ref "JP2") (pin "25") (pinfunction "25_25") (pintype "passive"))
    )
    (net (code "62") (name "unconnected-(JP2-Pad26)") (class "Default")
      (node (ref "JP2") (pin "26") (pinfunction "26_26") (pintype "passive"))
    )
    (net (code "63") (name "unconnected-(JP2-Pad27)") (class "Default")
      (node (ref "JP2") (pin "27") (pinfunction "27_27") (pintype "passive"))
    )
    (net (code "64") (name "unconnected-(JP2-Pad28)") (class "Default")
      (node (ref "JP2") (pin "28") (pinfunction "28_28") (pintype "passive"))
    )
    (net (code "65") (name "unconnected-(JP2-Pad29)") (class "Default")
      (node (ref "JP2") (pin "29") (pinfunction "29_29") (pintype "passive"))
    )
    (net (code "66") (name "unconnected-(JP2-Pad30)") (class "Default")
      (node (ref "JP2") (pin "30") (pinfunction "30_30") (pintype "passive"))
    )
    (net (code "67") (name "unconnected-(JP2-Pad32)") (class "Default")
      (node (ref "JP2") (pin "32") (pinfunction "32_32") (pintype "passive"))
    )
    (net (code "68") (name "unconnected-(LED2-C-PadK)") (class "Default")
      (node (ref "LED2") (pin "K") (pinfunction "C_K") (pintype "passive"))
    )
    (net (code "69") (name "unconnected-(LED2-PadA)") (class "Default")
      (node (ref "LED2") (pin "A") (pinfunction "A_A") (pintype "passive"))
    )
    (net (code "70") (name "unconnected-(LED3-C-PadK)") (class "Default")
      (node (ref "LED3") (pin "K") (pinfunction "C_K") (pintype "passive"))
    )
    (net (code "71") (name "unconnected-(LED3-PadA)") (class "Default")
      (node (ref "LED3") (pin "A") (pinfunction "A_A") (pintype "passive"))
    )
    (net (code "72") (name "unconnected-(LED4-C-PadK)") (class "Default")
      (node (ref "LED4") (pin "K") (pinfunction "C_K") (pintype "passive"))
    )
    (net (code "73") (name "unconnected-(LED4-PadA)") (class "Default")
      (node (ref "LED4") (pin "A") (pinfunction "A_A") (pintype "passive"))
    )
    (net (code "74") (name "unconnected-(LED5-C-PadK)") (class "Default")
      (node (ref "LED5") (pin "K") (pinfunction "C_K") (pintype "passive"))
    )
    (net (code "75") (name "unconnected-(LED5-PadA)") (class "Default")
      (node (ref "LED5") (pin "A") (pinfunction "A_A") (pintype "passive"))
    )
    (net (code "76") (name "unconnected-(LED6-C-PadK)") (class "Default")
      (node (ref "LED6") (pin "K") (pinfunction "C_K") (pintype "passive"))
    )
    (net (code "77") (name "unconnected-(LED6-PadA)") (class "Default")
      (node (ref "LED6") (pin "A") (pinfunction "A_A") (pintype "passive"))
    )
    (net (code "78") (name "unconnected-(LED7-C-PadK)") (class "Default")
      (node (ref "LED7") (pin "K") (pinfunction "C_K") (pintype "passive"))
    )
    (net (code "79") (name "unconnected-(LED7-PadA)") (class "Default")
      (node (ref "LED7") (pin "A") (pinfunction "A_A") (pintype "passive"))
    )
    (net (code "80") (name "unconnected-(LED8-C-PadK)") (class "Default")
      (node (ref "LED8") (pin "K") (pinfunction "C_K") (pintype "passive"))
    )
    (net (code "81") (name "unconnected-(LED8-PadA)") (class "Default")
      (node (ref "LED8") (pin "A") (pinfunction "A_A") (pintype "passive"))
    )
    (net (code "82") (name "unconnected-(LED9-C-PadK)") (class "Default")
      (node (ref "LED9") (pin "K") (pinfunction "C_K") (pintype "passive"))
    )
    (net (code "83") (name "unconnected-(LED9-PadA)") (class "Default")
      (node (ref "LED9") (pin "A") (pinfunction "A_A") (pintype "passive"))
    )
    (net (code "84") (name "unconnected-(LED10-C-PadK)") (class "Default")
      (node (ref "LED10") (pin "K") (pinfunction "C_K") (pintype "passive"))
    )
    (net (code "85") (name "unconnected-(LED10-PadA)") (class "Default")
      (node (ref "LED10") (pin "A") (pinfunction "A_A") (pintype "passive"))
    )
    (net (code "86") (name "unconnected-(LED11-C-PadK)") (class "Default")
      (node (ref "LED11") (pin "K") (pinfunction "C_K") (pintype "passive"))
    )
    (net (code "87") (name "unconnected-(LED11-PadA)") (class "Default")
      (node (ref "LED11") (pin "A") (pinfunction "A_A") (pintype "passive"))
    )
    (net (code "88") (name "unconnected-(LED12-C-PadK)") (class "Default")
      (node (ref "LED12") (pin "K") (pinfunction "C_K") (pintype "passive"))
    )
    (net (code "89") (name "unconnected-(LED12-PadA)") (class "Default")
      (node (ref "LED12") (pin "A") (pinfunction "A_A") (pintype "passive"))
    )
    (net (code "90") (name "unconnected-(LED13-C-PadK)") (class "Default")
      (node (ref "LED13") (pin "K") (pinfunction "C_K") (pintype "passive"))
    )
    (net (code "91") (name "unconnected-(LED13-PadA)") (class "Default")
      (node (ref "LED13") (pin "A") (pinfunction "A_A") (pintype "passive"))
    )
    (net (code "92") (name "unconnected-(LED14-C-PadK)") (class "Default")
      (node (ref "LED14") (pin "K") (pinfunction "C_K") (pintype "passive"))
    )
    (net (code "93") (name "unconnected-(LED14-PadA)") (class "Default")
      (node (ref "LED14") (pin "A") (pinfunction "A_A") (pintype "passive"))
    )
    (net (code "94") (name "unconnected-(LED15-C-PadK)") (class "Default")
      (node (ref "LED15") (pin "K") (pinfunction "C_K") (pintype "passive"))
    )
    (net (code "95") (name "unconnected-(LED15-PadA)") (class "Default")
      (node (ref "LED15") (pin "A") (pinfunction "A_A") (pintype "passive"))
    )
    (net (code "96") (name "unconnected-(LED16-C-PadK)") (class "Default")
      (node (ref "LED16") (pin "K") (pinfunction "C_K") (pintype "passive"))
    )
    (net (code "97") (name "unconnected-(LED16-PadA)") (class "Default")
      (node (ref "LED16") (pin "A") (pinfunction "A_A") (pintype "passive"))
    )
    (net (code "98") (name "unconnected-(LED17-C-PadK)") (class "Default")
      (node (ref "LED17") (pin "K") (pinfunction "C_K") (pintype "passive"))
    )
    (net (code "99") (name "unconnected-(LED17-PadA)") (class "Default")
      (node (ref "LED17") (pin "A") (pinfunction "A_A") (pintype "passive"))
    )
    (net (code "100") (name "unconnected-(LED18-C-PadK)") (class "Default")
      (node (ref "LED18") (pin "K") (pinfunction "C_K") (pintype "passive"))
    )
    (net (code "101") (name "unconnected-(LED18-PadA)") (class "Default")
      (node (ref "LED18") (pin "A") (pinfunction "A_A") (pintype "passive"))
    )
    (net (code "102") (name "unconnected-(LED19-C-PadK)") (class "Default")
      (node (ref "LED19") (pin "K") (pinfunction "C_K") (pintype "passive"))
    )
    (net (code "103") (name "unconnected-(LED19-PadA)") (class "Default")
      (node (ref "LED19") (pin "A") (pinfunction "A_A") (pintype "passive"))
    )
    (net (code "104") (name "unconnected-(LED20-C-PadK)") (class "Default")
      (node (ref "LED20") (pin "K") (pinfunction "C_K") (pintype "passive"))
    )
    (net (code "105") (name "unconnected-(LED20-PadA)") (class "Default")
      (node (ref "LED20") (pin "A") (pinfunction "A_A") (pintype "passive"))
    )
    (net (code "106") (name "unconnected-(LED21-C-PadK)") (class "Default")
      (node (ref "LED21") (pin "K") (pinfunction "C_K") (pintype "passive"))
    )
    (net (code "107") (name "unconnected-(LED21-PadA)") (class "Default")
      (node (ref "LED21") (pin "A") (pinfunction "A_A") (pintype "passive"))
    )
    (net (code "108") (name "unconnected-(LED22-C-PadK)") (class "Default")
      (node (ref "LED22") (pin "K") (pinfunction "C_K") (pintype "passive"))
    )
    (net (code "109") (name "unconnected-(LED22-PadA)") (class "Default")
      (node (ref "LED22") (pin "A") (pinfunction "A_A") (pintype "passive"))
    )
    (net (code "110") (name "unconnected-(LED23-C-PadK)") (class "Default")
      (node (ref "LED23") (pin "K") (pinfunction "C_K") (pintype "passive"))
    )
    (net (code "111") (name "unconnected-(LED23-PadA)") (class "Default")
      (node (ref "LED23") (pin "A") (pinfunction "A_A") (pintype "passive"))
    )
    (net (code "112") (name "unconnected-(LED24-C-PadK)") (class "Default")
      (node (ref "LED24") (pin "K") (pinfunction "C_K") (pintype "passive"))
    )
    (net (code "113") (name "unconnected-(LED24-PadA)") (class "Default")
      (node (ref "LED24") (pin "A") (pinfunction "A_A") (pintype "passive"))
    )
    (net (code "114") (name "unconnected-(LED25-C-PadK)") (class "Default")
      (node (ref "LED25") (pin "K") (pinfunction "C_K") (pintype "passive"))
    )
    (net (code "115") (name "unconnected-(LED25-PadA)") (class "Default")
      (node (ref "LED25") (pin "A") (pinfunction "A_A") (pintype "passive"))
    )
    (net (code "116") (name "unconnected-(LED26-C-PadK)") (class "Default")
      (node (ref "LED26") (pin "K") (pinfunction "C_K") (pintype "passive"))
    )
    (net (code "117") (name "unconnected-(LED26-PadA)") (class "Default")
      (node (ref "LED26") (pin "A") (pinfunction "A_A") (pintype "passive"))
    )
    (net (code "118") (name "unconnected-(LED27-C-PadK)") (class "Default")
      (node (ref "LED27") (pin "K") (pinfunction "C_K") (pintype "passive"))
    )
    (net (code "119") (name "unconnected-(LED27-PadA)") (class "Default")
      (node (ref "LED27") (pin "A") (pinfunction "A_A") (pintype "passive"))
    )
    (net (code "120") (name "unconnected-(LED28-C-PadK)") (class "Default")
      (node (ref "LED28") (pin "K") (pinfunction "C_K") (pintype "passive"))
    )
    (net (code "121") (name "unconnected-(LED28-PadA)") (class "Default")
      (node (ref "LED28") (pin "A") (pinfunction "A_A") (pintype "passive"))
    )
    (net (code "122") (name "unconnected-(LED29-C-PadK)") (class "Default")
      (node (ref "LED29") (pin "K") (pinfunction "C_K") (pintype "passive"))
    )
    (net (code "123") (name "unconnected-(LED29-PadA)") (class "Default")
      (node (ref "LED29") (pin "A") (pinfunction "A_A") (pintype "passive"))
    )
    (net (code "124") (name "unconnected-(LED30-C-PadK)") (class "Default")
      (node (ref "LED30") (pin "K") (pinfunction "C_K") (pintype "passive"))
    )
    (net (code "125") (name "unconnected-(LED30-PadA)") (class "Default")
      (node (ref "LED30") (pin "A") (pinfunction "A_A") (pintype "passive"))
    )
    (net (code "126") (name "unconnected-(LED31-C-PadK)") (class "Default")
      (node (ref "LED31") (pin "K") (pinfunction "C_K") (pintype "passive"))
    )
    (net (code "127") (name "unconnected-(LED31-PadA)") (class "Default")
      (node (ref "LED31") (pin "A") (pinfunction "A_A") (pintype "passive"))
    )
    (net (code "128") (name "unconnected-(LED32-C-PadK)") (class "Default")
      (node (ref "LED32") (pin "K") (pinfunction "C_K") (pintype "passive"))
    )
    (net (code "129") (name "unconnected-(LED32-PadA)") (class "Default")
      (node (ref "LED32") (pin "A") (pinfunction "A_A") (pintype "passive"))
    )
    (net (code "130") (name "unconnected-(LED33-C-PadK)") (class "Default")
      (node (ref "LED33") (pin "K") (pinfunction "C_K") (pintype "passive"))
    )
    (net (code "131") (name "unconnected-(LED33-PadA)") (class "Default")
      (node (ref "LED33") (pin "A") (pinfunction "A_A") (pintype "passive"))
    )
    (net (code "132") (name "unconnected-(LED34-C-PadK)") (class "Default")
      (node (ref "LED34") (pin "K") (pinfunction "C_K") (pintype "passive"))
    )
    (net (code "133") (name "unconnected-(LED34-PadA)") (class "Default")
      (node (ref "LED34") (pin "A") (pinfunction "A_A") (pintype "passive"))
    )
    (net (code "134") (name "unconnected-(LED35-C-PadK)") (class "Default")
      (node (ref "LED35") (pin "K") (pinfunction "C_K") (pintype "passive"))
    )
    (net (code "135") (name "unconnected-(LED35-PadA)") (class "Default")
      (node (ref "LED35") (pin "A") (pinfunction "A_A") (pintype "passive"))
    )
    (net (code "136") (name "unconnected-(LED36-C-PadK)") (class "Default")
      (node (ref "LED36") (pin "K") (pinfunction "C_K") (pintype "passive"))
    )
    (net (code "137") (name "unconnected-(LED36-PadA)") (class "Default")
      (node (ref "LED36") (pin "A") (pinfunction "A_A") (pintype "passive"))
    )
    (net (code "138") (name "unconnected-(LED37-C-PadK)") (class "Default")
      (node (ref "LED37") (pin "K") (pinfunction "C_K") (pintype "passive"))
    )
    (net (code "139") (name "unconnected-(LED37-PadA)") (class "Default")
      (node (ref "LED37") (pin "A") (pinfunction "A_A") (pintype "passive"))
    )
    (net (code "140") (name "unconnected-(LED38-C-PadK)") (class "Default")
      (node (ref "LED38") (pin "K") (pinfunction "C_K") (pintype "passive"))
    )
    (net (code "141") (name "unconnected-(LED38-PadA)") (class "Default")
      (node (ref "LED38") (pin "A") (pinfunction "A_A") (pintype "passive"))
    )
    (net (code "142") (name "unconnected-(LED39-C-PadK)") (class "Default")
      (node (ref "LED39") (pin "K") (pinfunction "C_K") (pintype "passive"))
    )
    (net (code "143") (name "unconnected-(LED39-PadA)") (class "Default")
      (node (ref "LED39") (pin "A") (pinfunction "A_A") (pintype "passive"))
    )
    (net (code "144") (name "unconnected-(LED40-C-PadK)") (class "Default")
      (node (ref "LED40") (pin "K") (pinfunction "C_K") (pintype "passive"))
    )
    (net (code "145") (name "unconnected-(LED40-PadA)") (class "Default")
      (node (ref "LED40") (pin "A") (pinfunction "A_A") (pintype "passive"))
    )
    (net (code "146") (name "unconnected-(LED41-C-PadK)") (class "Default")
      (node (ref "LED41") (pin "K") (pinfunction "C_K") (pintype "passive"))
    )
    (net (code "147") (name "unconnected-(LED41-PadA)") (class "Default")
      (node (ref "LED41") (pin "A") (pinfunction "A_A") (pintype "passive"))
    )
    (net (code "148") (name "unconnected-(LED42-C-PadK)") (class "Default")
      (node (ref "LED42") (pin "K") (pinfunction "C_K") (pintype "passive"))
    )
    (net (code "149") (name "unconnected-(LED42-PadA)") (class "Default")
      (node (ref "LED42") (pin "A") (pinfunction "A_A") (pintype "passive"))
    )
    (net (code "150") (name "unconnected-(LED43-C-PadK)") (class "Default")
      (node (ref "LED43") (pin "K") (pinfunction "C_K") (pintype "passive"))
    )
    (net (code "151") (name "unconnected-(LED43-PadA)") (class "Default")
      (node (ref "LED43") (pin "A") (pinfunction "A_A") (pintype "passive"))
    )
    (net (code "152") (name "unconnected-(LED44-C-PadK)") (class "Default")
      (node (ref "LED44") (pin "K") (pinfunction "C_K") (pintype "passive"))
    )
    (net (code "153") (name "unconnected-(LED44-PadA)") (class "Default")
      (node (ref "LED44") (pin "A") (pinfunction "A_A") (pintype "passive"))
    )
    (net (code "154") (name "unconnected-(LED45-C-PadK)") (class "Default")
      (node (ref "LED45") (pin "K") (pinfunction "C_K") (pintype "passive"))
    )
    (net (code "155") (name "unconnected-(LED45-PadA)") (class "Default")
      (node (ref "LED45") (pin "A") (pinfunction "A_A") (pintype "passive"))
    )
    (net (code "156") (name "unconnected-(LED46-C-PadK)") (class "Default")
      (node (ref "LED46") (pin "K") (pinfunction "C_K") (pintype "passive"))
    )
    (net (code "157") (name "unconnected-(LED46-PadA)") (class "Default")
      (node (ref "LED46") (pin "A") (pinfunction "A_A") (pintype "passive"))
    )
    (net (code "158") (name "unconnected-(LED47-C-PadK)") (class "Default")
      (node (ref "LED47") (pin "K") (pinfunction "C_K") (pintype "passive"))
    )
    (net (code "159") (name "unconnected-(LED47-PadA)") (class "Default")
      (node (ref "LED47") (pin "A") (pinfunction "A_A") (pintype "passive"))
    )
    (net (code "160") (name "unconnected-(LED48-C-PadK)") (class "Default")
      (node (ref "LED48") (pin "K") (pinfunction "C_K") (pintype "passive"))
    )
    (net (code "161") (name "unconnected-(LED48-PadA)") (class "Default")
      (node (ref "LED48") (pin "A") (pinfunction "A_A") (pintype "passive"))
    )
    (net (code "162") (name "unconnected-(LED49-C-PadK)") (class "Default")
      (node (ref "LED49") (pin "K") (pinfunction "C_K") (pintype "passive"))
    )
    (net (code "163") (name "unconnected-(LED49-PadA)") (class "Default")
      (node (ref "LED49") (pin "A") (pinfunction "A_A") (pintype "passive"))
    )
    (net (code "164") (name "unconnected-(LED50-C-PadK)") (class "Default")
      (node (ref "LED50") (pin "K") (pinfunction "C_K") (pintype "passive"))
    )
    (net (code "165") (name "unconnected-(LED50-PadA)") (class "Default")
      (node (ref "LED50") (pin "A") (pinfunction "A_A") (pintype "passive"))
    )
    (net (code "166") (name "unconnected-(LED51-C-PadK)") (class "Default")
      (node (ref "LED51") (pin "K") (pinfunction "C_K") (pintype "passive"))
    )
    (net (code "167") (name "unconnected-(LED51-PadA)") (class "Default")
      (node (ref "LED51") (pin "A") (pinfunction "A_A") (pintype "passive"))
    )
    (net (code "168") (name "unconnected-(LED52-C-PadK)") (class "Default")
      (node (ref "LED52") (pin "K") (pinfunction "C_K") (pintype "passive"))
    )
    (net (code "169") (name "unconnected-(LED52-PadA)") (class "Default")
      (node (ref "LED52") (pin "A") (pinfunction "A_A") (pintype "passive"))
    )
    (net (code "170") (name "unconnected-(LED53-C-PadK)") (class "Default")
      (node (ref "LED53") (pin "K") (pinfunction "C_K") (pintype "passive"))
    )
    (net (code "171") (name "unconnected-(LED53-PadA)") (class "Default")
      (node (ref "LED53") (pin "A") (pinfunction "A_A") (pintype "passive"))
    )
    (net (code "172") (name "unconnected-(LED54-C-PadK)") (class "Default")
      (node (ref "LED54") (pin "K") (pinfunction "C_K") (pintype "passive"))
    )
    (net (code "173") (name "unconnected-(LED54-PadA)") (class "Default")
      (node (ref "LED54") (pin "A") (pinfunction "A_A") (pintype "passive"))
    )
    (net (code "174") (name "unconnected-(LED55-C-PadK)") (class "Default")
      (node (ref "LED55") (pin "K") (pinfunction "C_K") (pintype "passive"))
    )
    (net (code "175") (name "unconnected-(LED55-PadA)") (class "Default")
      (node (ref "LED55") (pin "A") (pinfunction "A_A") (pintype "passive"))
    )
    (net (code "176") (name "unconnected-(LED56-C-PadK)") (class "Default")
      (node (ref "LED56") (pin "K") (pinfunction "C_K") (pintype "passive"))
    )
    (net (code "177") (name "unconnected-(LED56-PadA)") (class "Default")
      (node (ref "LED56") (pin "A") (pinfunction "A_A") (pintype "passive"))
    )
    (net (code "178") (name "unconnected-(LED57-C-PadK)") (class "Default")
      (node (ref "LED57") (pin "K") (pinfunction "C_K") (pintype "passive"))
    )
    (net (code "179") (name "unconnected-(LED57-PadA)") (class "Default")
      (node (ref "LED57") (pin "A") (pinfunction "A_A") (pintype "passive"))
    )
    (net (code "180") (name "unconnected-(LED58-C-PadK)") (class "Default")
      (node (ref "LED58") (pin "K") (pinfunction "C_K") (pintype "passive"))
    )
    (net (code "181") (name "unconnected-(LED58-PadA)") (class "Default")
      (node (ref "LED58") (pin "A") (pinfunction "A_A") (pintype "passive"))
    )
    (net (code "182") (name "unconnected-(LED59-C-PadK)") (class "Default")
      (node (ref "LED59") (pin "K") (pinfunction "C_K") (pintype "passive"))
    )
    (net (code "183") (name "unconnected-(LED59-PadA)") (class "Default")
      (node (ref "LED59") (pin "A") (pinfunction "A_A") (pintype "passive"))
    )
    (net (code "184") (name "unconnected-(LED60-C-PadK)") (class "Default")
      (node (ref "LED60") (pin "K") (pinfunction "C_K") (pintype "passive"))
    )
    (net (code "185") (name "unconnected-(LED60-PadA)") (class "Default")
      (node (ref "LED60") (pin "A") (pinfunction "A_A") (pintype "passive"))
    )
    (net (code "186") (name "unconnected-(LED61-C-PadK)") (class "Default")
      (node (ref "LED61") (pin "K") (pinfunction "C_K") (pintype "passive"))
    )
    (net (code "187") (name "unconnected-(LED61-PadA)") (class "Default")
      (node (ref "LED61") (pin "A") (pinfunction "A_A") (pintype "passive"))
    )
    (net (code "188") (name "unconnected-(LED62-C-PadK)") (class "Default")
      (node (ref "LED62") (pin "K") (pinfunction "C_K") (pintype "passive"))
    )
    (net (code "189") (name "unconnected-(LED62-PadA)") (class "Default")
      (node (ref "LED62") (pin "A") (pinfunction "A_A") (pintype "passive"))
    )
    (net (code "190") (name "unconnected-(LED63-C-PadK)") (class "Default")
      (node (ref "LED63") (pin "K") (pinfunction "C_K") (pintype "passive"))
    )
    (net (code "191") (name "unconnected-(LED63-PadA)") (class "Default")
      (node (ref "LED63") (pin "A") (pinfunction "A_A") (pintype "passive"))
    )
    (net (code "192") (name "unconnected-(LED64-C-PadK)") (class "Default")
      (node (ref "LED64") (pin "K") (pinfunction "C_K") (pintype "passive"))
    )
    (net (code "193") (name "unconnected-(LED64-PadA)") (class "Default")
      (node (ref "LED64") (pin "A") (pinfunction "A_A") (pintype "passive"))
    )
    (net (code "194") (name "unconnected-(LED65-C-PadK)") (class "Default")
      (node (ref "LED65") (pin "K") (pinfunction "C_K") (pintype "passive"))
    )
    (net (code "195") (name "unconnected-(LED65-PadA)") (class "Default")
      (node (ref "LED65") (pin "A") (pinfunction "A_A") (pintype "passive"))
    )
    (net (code "196") (name "unconnected-(LED66-C-PadK)") (class "Default")
      (node (ref "LED66") (pin "K") (pinfunction "C_K") (pintype "passive"))
    )
    (net (code "197") (name "unconnected-(LED66-PadA)") (class "Default")
      (node (ref "LED66") (pin "A") (pinfunction "A_A") (pintype "passive"))
    )
    (net (code "198") (name "unconnected-(LED67-C-PadK)") (class "Default")
      (node (ref "LED67") (pin "K") (pinfunction "C_K") (pintype "passive"))
    )
    (net (code "199") (name "unconnected-(LED67-PadA)") (class "Default")
      (node (ref "LED67") (pin "A") (pinfunction "A_A") (pintype "passive"))
    )
    (net (code "200") (name "unconnected-(LED68-C-PadK)") (class "Default")
      (node (ref "LED68") (pin "K") (pinfunction "C_K") (pintype "passive"))
    )
    (net (code "201") (name "unconnected-(LED68-PadA)") (class "Default")
      (node (ref "LED68") (pin "A") (pinfunction "A_A") (pintype "passive"))
    )
    (net (code "202") (name "unconnected-(LED69-C-PadK)") (class "Default")
      (node (ref "LED69") (pin "K") (pinfunction "C_K") (pintype "passive"))
    )
    (net (code "203") (name "unconnected-(LED69-PadA)") (class "Default")
      (node (ref "LED69") (pin "A") (pinfunction "A_A") (pintype "passive"))
    )
    (net (code "204") (name "unconnected-(LED70-C-PadK)") (class "Default")
      (node (ref "LED70") (pin "K") (pinfunction "C_K") (pintype "passive"))
    )
    (net (code "205") (name "unconnected-(LED70-PadA)") (class "Default")
      (node (ref "LED70") (pin "A") (pinfunction "A_A") (pintype "passive"))
    )
    (net (code "206") (name "unconnected-(LED71-C-PadK)") (class "Default")
      (node (ref "LED71") (pin "K") (pinfunction "C_K") (pintype "passive"))
    )
    (net (code "207") (name "unconnected-(LED71-PadA)") (class "Default")
      (node (ref "LED71") (pin "A") (pinfunction "A_A") (pintype "passive"))
    )
    (net (code "208") (name "unconnected-(LED72-C-PadK)") (class "Default")
      (node (ref "LED72") (pin "K") (pinfunction "C_K") (pintype "passive"))
    )
    (net (code "209") (name "unconnected-(LED72-PadA)") (class "Default")
      (node (ref "LED72") (pin "A") (pinfunction "A_A") (pintype "passive"))
    )
    (net (code "210") (name "unconnected-(LED73-C-PadK)") (class "Default")
      (node (ref "LED73") (pin "K") (pinfunction "C_K") (pintype "passive"))
    )
    (net (code "211") (name "unconnected-(LED73-PadA)") (class "Default")
      (node (ref "LED73") (pin "A") (pinfunction "A_A") (pintype "passive"))
    )
    (net (code "212") (name "unconnected-(LED74-C-PadK)") (class "Default")
      (node (ref "LED74") (pin "K") (pinfunction "C_K") (pintype "passive"))
    )
    (net (code "213") (name "unconnected-(LED74-PadA)") (class "Default")
      (node (ref "LED74") (pin "A") (pinfunction "A_A") (pintype "passive"))
    )
    (net (code "214") (name "unconnected-(LED75-C-PadK)") (class "Default")
      (node (ref "LED75") (pin "K") (pinfunction "C_K") (pintype "passive"))
    )
    (net (code "215") (name "unconnected-(LED75-PadA)") (class "Default")
      (node (ref "LED75") (pin "A") (pinfunction "A_A") (pintype "passive"))
    )
    (net (code "216") (name "unconnected-(LED76-C-PadK)") (class "Default")
      (node (ref "LED76") (pin "K") (pinfunction "C_K") (pintype "passive"))
    )
    (net (code "217") (name "unconnected-(LED76-PadA)") (class "Default")
      (node (ref "LED76") (pin "A") (pinfunction "A_A") (pintype "passive"))
    )
    (net (code "218") (name "unconnected-(LED77-C-PadK)") (class "Default")
      (node (ref "LED77") (pin "K") (pinfunction "C_K") (pintype "passive"))
    )
    (net (code "219") (name "unconnected-(LED77-PadA)") (class "Default")
      (node (ref "LED77") (pin "A") (pinfunction "A_A") (pintype "passive"))
    )
    (net (code "220") (name "unconnected-(LED78-C-PadK)") (class "Default")
      (node (ref "LED78") (pin "K") (pinfunction "C_K") (pintype "passive"))
    )
    (net (code "221") (name "unconnected-(LED78-PadA)") (class "Default")
      (node (ref "LED78") (pin "A") (pinfunction "A_A") (pintype "passive"))
    )
    (net (code "222") (name "unconnected-(LED79-C-PadK)") (class "Default")
      (node (ref "LED79") (pin "K") (pinfunction "C_K") (pintype "passive"))
    )
    (net (code "223") (name "unconnected-(LED79-PadA)") (class "Default")
      (node (ref "LED79") (pin "A") (pinfunction "A_A") (pintype "passive"))
    )
    (net (code "224") (name "unconnected-(LED80-C-PadK)") (class "Default")
      (node (ref "LED80") (pin "K") (pinfunction "C_K") (pintype "passive"))
    )
    (net (code "225") (name "unconnected-(LED80-PadA)") (class "Default")
      (node (ref "LED80") (pin "A") (pinfunction "A_A") (pintype "passive"))
    )
    (net (code "226") (name "unconnected-(LED81-C-PadK)") (class "Default")
      (node (ref "LED81") (pin "K") (pinfunction "C_K") (pintype "passive"))
    )
    (net (code "227") (name "unconnected-(LED81-PadA)") (class "Default")
      (node (ref "LED81") (pin "A") (pinfunction "A_A") (pintype "passive"))
    )
    (net (code "228") (name "unconnected-(LED82-C-PadK)") (class "Default")
      (node (ref "LED82") (pin "K") (pinfunction "C_K") (pintype "passive"))
    )
    (net (code "229") (name "unconnected-(LED82-PadA)") (class "Default")
      (node (ref "LED82") (pin "A") (pinfunction "A_A") (pintype "passive"))
    )
    (net (code "230") (name "unconnected-(LED83-C-PadK)") (class "Default")
      (node (ref "LED83") (pin "K") (pinfunction "C_K") (pintype "passive"))
    )
    (net (code "231") (name "unconnected-(LED83-PadA)") (class "Default")
      (node (ref "LED83") (pin "A") (pinfunction "A_A") (pintype "passive"))
    )
    (net (code "232") (name "unconnected-(LED84-C-PadK)") (class "Default")
      (node (ref "LED84") (pin "K") (pinfunction "C_K") (pintype "passive"))
    )
    (net (code "233") (name "unconnected-(LED84-PadA)") (class "Default")
      (node (ref "LED84") (pin "A") (pinfunction "A_A") (pintype "passive"))
    )
    (net (code "234") (name "unconnected-(LED85-C-PadK)") (class "Default")
      (node (ref "LED85") (pin "K") (pinfunction "C_K") (pintype "passive"))
    )
    (net (code "235") (name "unconnected-(LED85-PadA)") (class "Default")
      (node (ref "LED85") (pin "A") (pinfunction "A_A") (pintype "passive"))
    )
    (net (code "236") (name "unconnected-(LED86-C-PadK)") (class "Default")
      (node (ref "LED86") (pin "K") (pinfunction "C_K") (pintype "passive"))
    )
    (net (code "237") (name "unconnected-(LED86-PadA)") (class "Default")
      (node (ref "LED86") (pin "A") (pinfunction "A_A") (pintype "passive"))
    )
    (net (code "238") (name "unconnected-(LED87-C-PadK)") (class "Default")
      (node (ref "LED87") (pin "K") (pinfunction "C_K") (pintype "passive"))
    )
    (net (code "239") (name "unconnected-(LED87-PadA)") (class "Default")
      (node (ref "LED87") (pin "A") (pinfunction "A_A") (pintype "passive"))
    )
    (net (code "240") (name "unconnected-(LED88-C-PadK)") (class "Default")
      (node (ref "LED88") (pin "K") (pinfunction "C_K") (pintype "passive"))
    )
    (net (code "241") (name "unconnected-(LED88-PadA)") (class "Default")
      (node (ref "LED88") (pin "A") (pinfunction "A_A") (pintype "passive"))
    )
    (net (code "242") (name "unconnected-(LED89-C-PadK)") (class "Default")
      (node (ref "LED89") (pin "K") (pinfunction "C_K") (pintype "passive"))
    )
    (net (code "243") (name "unconnected-(LED89-PadA)") (class "Default")
      (node (ref "LED89") (pin "A") (pinfunction "A_A") (pintype "passive"))
    )
    (net (code "244") (name "unconnected-(LED90-C-PadK)") (class "Default")
      (node (ref "LED90") (pin "K") (pinfunction "C_K") (pintype "passive"))
    )
    (net (code "245") (name "unconnected-(LED90-PadA)") (class "Default")
      (node (ref "LED90") (pin "A") (pinfunction "A_A") (pintype "passive"))
    )
    (net (code "246") (name "unconnected-(LED91-C-PadK)") (class "Default")
      (node (ref "LED91") (pin "K") (pinfunction "C_K") (pintype "passive"))
    )
    (net (code "247") (name "unconnected-(LED91-PadA)") (class "Default")
      (node (ref "LED91") (pin "A") (pinfunction "A_A") (pintype "passive"))
    )
    (net (code "248") (name "unconnected-(LED92-C-PadK)") (class "Default")
      (node (ref "LED92") (pin "K") (pinfunction "C_K") (pintype "passive"))
    )
    (net (code "249") (name "unconnected-(LED92-PadA)") (class "Default")
      (node (ref "LED92") (pin "A") (pinfunction "A_A") (pintype "passive"))
    )
    (net (code "250") (name "unconnected-(LED93-C-PadK)") (class "Default")
      (node (ref "LED93") (pin "K") (pinfunction "C_K") (pintype "passive"))
    )
    (net (code "251") (name "unconnected-(LED93-PadA)") (class "Default")
      (node (ref "LED93") (pin "A") (pinfunction "A_A") (pintype "passive"))
    )
    (net (code "252") (name "unconnected-(LED94-C-PadK)") (class "Default")
      (node (ref "LED94") (pin "K") (pinfunction "C_K") (pintype "passive"))
    )
    (net (code "253") (name "unconnected-(LED94-PadA)") (class "Default")
      (node (ref "LED94") (pin "A") (pinfunction "A_A") (pintype "passive"))
    )
    (net (code "254") (name "unconnected-(LED95-C-PadK)") (class "Default")
      (node (ref "LED95") (pin "K") (pinfunction "C_K") (pintype "passive"))
    )
    (net (code "255") (name "unconnected-(LED95-PadA)") (class "Default")
      (node (ref "LED95") (pin "A") (pinfunction "A_A") (pintype "passive"))
    )
    (net (code "256") (name "unconnected-(LED96-C-PadK)") (class "Default")
      (node (ref "LED96") (pin "K") (pinfunction "C_K") (pintype "passive"))
    )
    (net (code "257") (name "unconnected-(LED96-PadA)") (class "Default")
      (node (ref "LED96") (pin "A") (pinfunction "A_A") (pintype "passive"))
    )
    (net (code "258") (name "unconnected-(LED97-C-PadK)") (class "Default")
      (node (ref "LED97") (pin "K") (pinfunction "C_K") (pintype "passive"))
    )
    (net (code "259") (name "unconnected-(LED97-PadA)") (class "Default")
      (node (ref "LED97") (pin "A") (pinfunction "A_A") (pintype "passive"))
    )
    (net (code "260") (name "unconnected-(LED98-C-PadK)") (class "Default")
      (node (ref "LED98") (pin "K") (pinfunction "C_K") (pintype "passive"))
    )
    (net (code "261") (name "unconnected-(LED98-PadA)") (class "Default")
      (node (ref "LED98") (pin "A") (pinfunction "A_A") (pintype "passive"))
    )
    (net (code "262") (name "unconnected-(LED99-C-PadK)") (class "Default")
      (node (ref "LED99") (pin "K") (pinfunction "C_K") (pintype "passive"))
    )
    (net (code "263") (name "unconnected-(LED99-PadA)") (class "Default")
      (node (ref "LED99") (pin "A") (pinfunction "A_A") (pintype "passive"))
    )
    (net (code "264") (name "unconnected-(LED100-C-PadK)") (class "Default")
      (node (ref "LED100") (pin "K") (pinfunction "C_K") (pintype "passive"))
    )
    (net (code "265") (name "unconnected-(LED100-PadA)") (class "Default")
      (node (ref "LED100") (pin "A") (pinfunction "A_A") (pintype "passive"))
    )
    (net (code "266") (name "unconnected-(LED101-C-PadK)") (class "Default")
      (node (ref "LED101") (pin "K") (pinfunction "C_K") (pintype "passive"))
    )
    (net (code "267") (name "unconnected-(LED101-PadA)") (class "Default")
      (node (ref "LED101") (pin "A") (pinfunction "A_A") (pintype "passive"))
    )
    (net (code "268") (name "unconnected-(LED102-C-PadK)") (class "Default")
      (node (ref "LED102") (pin "K") (pinfunction "C_K") (pintype "passive"))
    )
    (net (code "269") (name "unconnected-(LED102-PadA)") (class "Default")
      (node (ref "LED102") (pin "A") (pinfunction "A_A") (pintype "passive"))
    )
    (net (code "270") (name "unconnected-(LED103-C-PadK)") (class "Default")
      (node (ref "LED103") (pin "K") (pinfunction "C_K") (pintype "passive"))
    )
    (net (code "271") (name "unconnected-(LED103-PadA)") (class "Default")
      (node (ref "LED103") (pin "A") (pinfunction "A_A") (pintype "passive"))
    )
    (net (code "272") (name "unconnected-(LED104-C-PadK)") (class "Default")
      (node (ref "LED104") (pin "K") (pinfunction "C_K") (pintype "passive"))
    )
    (net (code "273") (name "unconnected-(LED104-PadA)") (class "Default")
      (node (ref "LED104") (pin "A") (pinfunction "A_A") (pintype "passive"))
    )
    (net (code "274") (name "unconnected-(LED105-C-PadK)") (class "Default")
      (node (ref "LED105") (pin "K") (pinfunction "C_K") (pintype "passive"))
    )
    (net (code "275") (name "unconnected-(LED105-PadA)") (class "Default")
      (node (ref "LED105") (pin "A") (pinfunction "A_A") (pintype "passive"))
    )
    (net (code "276") (name "unconnected-(LED106-C-PadK)") (class "Default")
      (node (ref "LED106") (pin "K") (pinfunction "C_K") (pintype "passive"))
    )
    (net (code "277") (name "unconnected-(LED106-PadA)") (class "Default")
      (node (ref "LED106") (pin "A") (pinfunction "A_A") (pintype "passive"))
    )
    (net (code "278") (name "unconnected-(LED107-C-PadK)") (class "Default")
      (node (ref "LED107") (pin "K") (pinfunction "C_K") (pintype "passive"))
    )
    (net (code "279") (name "unconnected-(LED107-PadA)") (class "Default")
      (node (ref "LED107") (pin "A") (pinfunction "A_A") (pintype "passive"))
    )
    (net (code "280") (name "unconnected-(LED108-C-PadK)") (class "Default")
      (node (ref "LED108") (pin "K") (pinfunction "C_K") (pintype "passive"))
    )
    (net (code "281") (name "unconnected-(LED108-PadA)") (class "Default")
      (node (ref "LED108") (pin "A") (pinfunction "A_A") (pintype "passive"))
    )
    (net (code "282") (name "unconnected-(LED109-C-PadK)") (class "Default")
      (node (ref "LED109") (pin "K") (pinfunction "C_K") (pintype "passive"))
    )
    (net (code "283") (name "unconnected-(LED109-PadA)") (class "Default")
      (node (ref "LED109") (pin "A") (pinfunction "A_A") (pintype "passive"))
    )
    (net (code "284") (name "unconnected-(LED110-C-PadK)") (class "Default")
      (node (ref "LED110") (pin "K") (pinfunction "C_K") (pintype "passive"))
    )
    (net (code "285") (name "unconnected-(LED110-PadA)") (class "Default")
      (node (ref "LED110") (pin "A") (pinfunction "A_A") (pintype "passive"))
    )
    (net (code "286") (name "unconnected-(LED111-C-PadK)") (class "Default")
      (node (ref "LED111") (pin "K") (pinfunction "C_K") (pintype "passive"))
    )
    (net (code "287") (name "unconnected-(LED111-PadA)") (class "Default")
      (node (ref "LED111") (pin "A") (pinfunction "A_A") (pintype "passive"))
    )
    (net (code "288") (name "unconnected-(LED112-C-PadK)") (class "Default")
      (node (ref "LED112") (pin "K") (pinfunction "C_K") (pintype "passive"))
    )
    (net (code "289") (name "unconnected-(LED112-PadA)") (class "Default")
      (node (ref "LED112") (pin "A") (pinfunction "A_A") (pintype "passive"))
    )
    (net (code "290") (name "unconnected-(LED113-C-PadK)") (class "Default")
      (node (ref "LED113") (pin "K") (pinfunction "C_K") (pintype "passive"))
    )
    (net (code "291") (name "unconnected-(LED113-PadA)") (class "Default")
      (node (ref "LED113") (pin "A") (pinfunction "A_A") (pintype "passive"))
    )
    (net (code "292") (name "unconnected-(LED114-C-PadK)") (class "Default")
      (node (ref "LED114") (pin "K") (pinfunction "C_K") (pintype "passive"))
    )
    (net (code "293") (name "unconnected-(LED114-PadA)") (class "Default")
      (node (ref "LED114") (pin "A") (pinfunction "A_A") (pintype "passive"))
    )
    (net (code "294") (name "unconnected-(LED115-C-PadK)") (class "Default")
      (node (ref "LED115") (pin "K") (pinfunction "C_K") (pintype "passive"))
    )
    (net (code "295") (name "unconnected-(LED115-PadA)") (class "Default")
      (node (ref "LED115") (pin "A") (pinfunction "A_A") (pintype "passive"))
    )
    (net (code "296") (name "unconnected-(LED116-C-PadK)") (class "Default")
      (node (ref "LED116") (pin "K") (pinfunction "C_K") (pintype "passive"))
    )
    (net (code "297") (name "unconnected-(LED116-PadA)") (class "Default")
      (node (ref "LED116") (pin "A") (pinfunction "A_A") (pintype "passive"))
    )
    (net (code "298") (name "unconnected-(LED117-C-PadK)") (class "Default")
      (node (ref "LED117") (pin "K") (pinfunction "C_K") (pintype "passive"))
    )
    (net (code "299") (name "unconnected-(LED117-PadA)") (class "Default")
      (node (ref "LED117") (pin "A") (pinfunction "A_A") (pintype "passive"))
    )
    (net (code "300") (name "unconnected-(LED118-C-PadK)") (class "Default")
      (node (ref "LED118") (pin "K") (pinfunction "C_K") (pintype "passive"))
    )
    (net (code "301") (name "unconnected-(LED118-PadA)") (class "Default")
      (node (ref "LED118") (pin "A") (pinfunction "A_A") (pintype "passive"))
    )
    (net (code "302") (name "unconnected-(LED119-C-PadK)") (class "Default")
      (node (ref "LED119") (pin "K") (pinfunction "C_K") (pintype "passive"))
    )
    (net (code "303") (name "unconnected-(LED119-PadA)") (class "Default")
      (node (ref "LED119") (pin "A") (pinfunction "A_A") (pintype "passive"))
    )
    (net (code "304") (name "unconnected-(LED120-C-PadK)") (class "Default")
      (node (ref "LED120") (pin "K") (pinfunction "C_K") (pintype "passive"))
    )
    (net (code "305") (name "unconnected-(LED120-PadA)") (class "Default")
      (node (ref "LED120") (pin "A") (pinfunction "A_A") (pintype "passive"))
    )
    (net (code "306") (name "unconnected-(LED121-C-PadK)") (class "Default")
      (node (ref "LED121") (pin "K") (pinfunction "C_K") (pintype "passive"))
    )
    (net (code "307") (name "unconnected-(LED121-PadA)") (class "Default")
      (node (ref "LED121") (pin "A") (pinfunction "A_A") (pintype "passive"))
    )
    (net (code "308") (name "unconnected-(LED122-C-PadK)") (class "Default")
      (node (ref "LED122") (pin "K") (pinfunction "C_K") (pintype "passive"))
    )
    (net (code "309") (name "unconnected-(LED122-PadA)") (class "Default")
      (node (ref "LED122") (pin "A") (pinfunction "A_A") (pintype "passive"))
    )
    (net (code "310") (name "unconnected-(LED123-C-PadK)") (class "Default")
      (node (ref "LED123") (pin "K") (pinfunction "C_K") (pintype "passive"))
    )
    (net (code "311") (name "unconnected-(LED123-PadA)") (class "Default")
      (node (ref "LED123") (pin "A") (pinfunction "A_A") (pintype "passive"))
    )
    (net (code "312") (name "unconnected-(LED124-C-PadK)") (class "Default")
      (node (ref "LED124") (pin "K") (pinfunction "C_K") (pintype "passive"))
    )
    (net (code "313") (name "unconnected-(LED124-PadA)") (class "Default")
      (node (ref "LED124") (pin "A") (pinfunction "A_A") (pintype "passive"))
    )
    (net (code "314") (name "unconnected-(LED125-C-PadK)") (class "Default")
      (node (ref "LED125") (pin "K") (pinfunction "C_K") (pintype "passive"))
    )
    (net (code "315") (name "unconnected-(LED125-PadA)") (class "Default")
      (node (ref "LED125") (pin "A") (pinfunction "A_A") (pintype "passive"))
    )
    (net (code "316") (name "unconnected-(LED126-C-PadK)") (class "Default")
      (node (ref "LED126") (pin "K") (pinfunction "C_K") (pintype "passive"))
    )
    (net (code "317") (name "unconnected-(LED126-PadA)") (class "Default")
      (node (ref "LED126") (pin "A") (pinfunction "A_A") (pintype "passive"))
    )
    (net (code "318") (name "unconnected-(LED127-C-PadK)") (class "Default")
      (node (ref "LED127") (pin "K") (pinfunction "C_K") (pintype "passive"))
    )
    (net (code "319") (name "unconnected-(LED127-PadA)") (class "Default")
      (node (ref "LED127") (pin "A") (pinfunction "A_A") (pintype "passive"))
    )
    (net (code "320") (name "unconnected-(LED128-C-PadK)") (class "Default")
      (node (ref "LED128") (pin "K") (pinfunction "C_K") (pintype "passive"))
    )
    (net (code "321") (name "unconnected-(LED128-PadA)") (class "Default")
      (node (ref "LED128") (pin "A") (pinfunction "A_A") (pintype "passive"))
    )
    (net (code "322") (name "unconnected-(LED129-C-PadK)") (class "Default")
      (node (ref "LED129") (pin "K") (pinfunction "C_K") (pintype "passive"))
    )
    (net (code "323") (name "unconnected-(LED129-PadA)") (class "Default")
      (node (ref "LED129") (pin "A") (pinfunction "A_A") (pintype "passive"))
    )
    (net (code "324") (name "unconnected-(LED130-C-PadK)") (class "Default")
      (node (ref "LED130") (pin "K") (pinfunction "C_K") (pintype "passive"))
    )
    (net (code "325") (name "unconnected-(LED130-PadA)") (class "Default")
      (node (ref "LED130") (pin "A") (pinfunction "A_A") (pintype "passive"))
    )
    (net (code "326") (name "unconnected-(LED131-C-PadK)") (class "Default")
      (node (ref "LED131") (pin "K") (pinfunction "C_K") (pintype "passive"))
    )
    (net (code "327") (name "unconnected-(LED131-PadA)") (class "Default")
      (node (ref "LED131") (pin "A") (pinfunction "A_A") (pintype "passive"))
    )
    (net (code "328") (name "unconnected-(LED132-C-PadK)") (class "Default")
      (node (ref "LED132") (pin "K") (pinfunction "C_K") (pintype "passive"))
    )
    (net (code "329") (name "unconnected-(LED132-PadA)") (class "Default")
      (node (ref "LED132") (pin "A") (pinfunction "A_A") (pintype "passive"))
    )
    (net (code "330") (name "unconnected-(LED133-C-PadK)") (class "Default")
      (node (ref "LED133") (pin "K") (pinfunction "C_K") (pintype "passive"))
    )
    (net (code "331") (name "unconnected-(LED133-PadA)") (class "Default")
      (node (ref "LED133") (pin "A") (pinfunction "A_A") (pintype "passive"))
    )
    (net (code "332") (name "unconnected-(LED134-C-PadK)") (class "Default")
      (node (ref "LED134") (pin "K") (pinfunction "C_K") (pintype "passive"))
    )
    (net (code "333") (name "unconnected-(LED134-PadA)") (class "Default")
      (node (ref "LED134") (pin "A") (pinfunction "A_A") (pintype "passive"))
    )
    (net (code "334") (name "unconnected-(LED135-C-PadK)") (class "Default")
      (node (ref "LED135") (pin "K") (pinfunction "C_K") (pintype "passive"))
    )
    (net (code "335") (name "unconnected-(LED135-PadA)") (class "Default")
      (node (ref "LED135") (pin "A") (pinfunction "A_A") (pintype "passive"))
    )
    (net (code "336") (name "unconnected-(LED136-C-PadK)") (class "Default")
      (node (ref "LED136") (pin "K") (pinfunction "C_K") (pintype "passive"))
    )
    (net (code "337") (name "unconnected-(LED136-PadA)") (class "Default")
      (node (ref "LED136") (pin "A") (pinfunction "A_A") (pintype "passive"))
    )
    (net (code "338") (name "unconnected-(LED137-C-PadK)") (class "Default")
      (node (ref "LED137") (pin "K") (pinfunction "C_K") (pintype "passive"))
    )
    (net (code "339") (name "unconnected-(LED137-PadA)") (class "Default")
      (node (ref "LED137") (pin "A") (pinfunction "A_A") (pintype "passive"))
    )
    (net (code "340") (name "unconnected-(LED138-C-PadK)") (class "Default")
      (node (ref "LED138") (pin "K") (pinfunction "C_K") (pintype "passive"))
    )
    (net (code "341") (name "unconnected-(LED138-PadA)") (class "Default")
      (node (ref "LED138") (pin "A") (pinfunction "A_A") (pintype "passive"))
    )
    (net (code "342") (name "unconnected-(LED139-C-PadK)") (class "Default")
      (node (ref "LED139") (pin "K") (pinfunction "C_K") (pintype "passive"))
    )
    (net (code "343") (name "unconnected-(LED139-PadA)") (class "Default")
      (node (ref "LED139") (pin "A") (pinfunction "A_A") (pintype "passive"))
    )
    (net (code "344") (name "unconnected-(LED140-C-PadK)") (class "Default")
      (node (ref "LED140") (pin "K") (pinfunction "C_K") (pintype "passive"))
    )
    (net (code "345") (name "unconnected-(LED140-PadA)") (class "Default")
      (node (ref "LED140") (pin "A") (pinfunction "A_A") (pintype "passive"))
    )
    (net (code "346") (name "unconnected-(LED141-C-PadK)") (class "Default")
      (node (ref "LED141") (pin "K") (pinfunction "C_K") (pintype "passive"))
    )
    (net (code "347") (name "unconnected-(LED141-PadA)") (class "Default")
      (node (ref "LED141") (pin "A") (pinfunction "A_A") (pintype "passive"))
    )
    (net (code "348") (name "unconnected-(LED142-C-PadK)") (class "Default")
      (node (ref "LED142") (pin "K") (pinfunction "C_K") (pintype "passive"))
    )
    (net (code "349") (name "unconnected-(LED142-PadA)") (class "Default")
      (node (ref "LED142") (pin "A") (pinfunction "A_A") (pintype "passive"))
    )
    (net (code "350") (name "unconnected-(LED143-C-PadK)") (class "Default")
      (node (ref "LED143") (pin "K") (pinfunction "C_K") (pintype "passive"))
    )
    (net (code "351") (name "unconnected-(LED143-PadA)") (class "Default")
      (node (ref "LED143") (pin "A") (pinfunction "A_A") (pintype "passive"))
    )
    (net (code "352") (name "unconnected-(LED144-C-PadK)") (class "Default")
      (node (ref "LED144") (pin "K") (pinfunction "C_K") (pintype "passive"))
    )
    (net (code "353") (name "unconnected-(LED144-PadA)") (class "Default")
      (node (ref "LED144") (pin "A") (pinfunction "A_A") (pintype "passive"))
    )
    (net (code "354") (name "unconnected-(LED145-C-PadK)") (class "Default")
      (node (ref "LED145") (pin "K") (pinfunction "C_K") (pintype "passive"))
    )
    (net (code "355") (name "unconnected-(LED145-PadA)") (class "Default")
      (node (ref "LED145") (pin "A") (pinfunction "A_A") (pintype "passive"))
    )
    (net (code "356") (name "unconnected-(U$1-Pad1)") (class "Default")
      (node (ref "U$1") (pin "1") (pinfunction "1_1") (pintype "bidirectional"))
    )
  )
)
